# Sheet1.net
KiCad netlist of a schematic drawn in Altium Designer
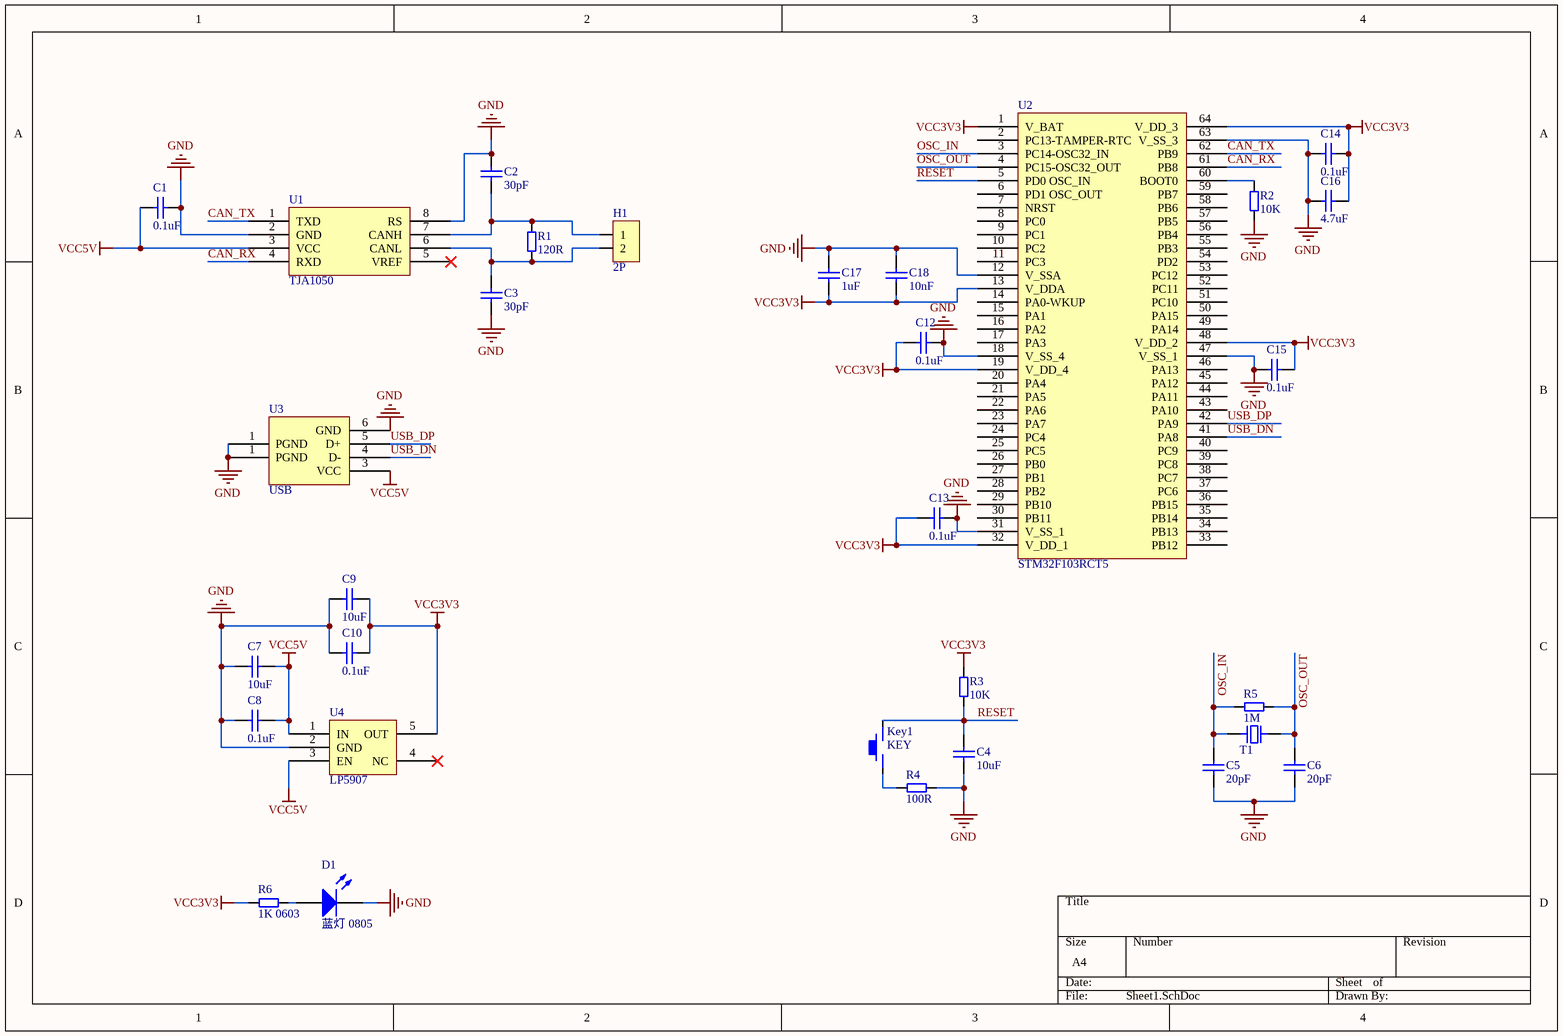
[diagram p0: Sheet1.SchDoc]

(export (version "E")
  (design (tool "Eeschema 10.0.6"))
  (components
    (comp (ref "C1")
      (value "0.1uF")
      (footprint "C1206")
      (description "贴片电容")
      (libsource (lib "WTR-SCH_LIB") (part "C"))
    )
    (comp (ref "C2")
      (value "30pF")
      (footprint "C1206")
      (description "贴片电容")
      (libsource (lib "WTR-SCH_LIB") (part "C"))
    )
    (comp (ref "C3")
      (value "30pF")
      (footprint "C1206")
      (description "贴片电容")
      (libsource (lib "WTR-SCH_LIB") (part "C"))
    )
    (comp (ref "C4")
      (value "10uF")
      (footprint "C1206")
      (description "贴片电容")
      (libsource (lib "WTR-SCH_LIB") (part "C"))
    )
    (comp (ref "C5")
      (value "20pF")
      (footprint "C1206")
      (description "贴片电容")
      (libsource (lib "WTR-SCH_LIB") (part "C"))
    )
    (comp (ref "C6")
      (value "20pF")
      (footprint "C1206")
      (description "贴片电容")
      (libsource (lib "WTR-SCH_LIB") (part "C"))
    )
    (comp (ref "C7")
      (value "10uF")
      (footprint "C1206")
      (description "贴片电容")
      (libsource (lib "WTR-SCH_LIB") (part "C"))
    )
    (comp (ref "C8")
      (value "0.1uF")
      (footprint "C1206")
      (description "贴片电容")
      (libsource (lib "WTR-SCH_LIB") (part "C"))
    )
    (comp (ref "C9")
      (value "10uF")
      (footprint "C1206")
      (description "贴片电容")
      (libsource (lib "WTR-SCH_LIB") (part "C"))
    )
    (comp (ref "C10")
      (value "0.1uF")
      (footprint "C1206")
      (description "贴片电容")
      (libsource (lib "WTR-SCH_LIB") (part "C"))
    )
    (comp (ref "C12")
      (value "0.1uF")
      (footprint "C1206")
      (description "贴片电容")
      (libsource (lib "WTR-SCH_LIB") (part "C"))
    )
    (comp (ref "C13")
      (value "0.1uF")
      (footprint "C1206")
      (description "贴片电容")
      (libsource (lib "WTR-SCH_LIB") (part "C"))
    )
    (comp (ref "C14")
      (value "0.1uF")
      (footprint "C1206")
      (description "贴片电容")
      (libsource (lib "WTR-SCH_LIB") (part "C"))
    )
    (comp (ref "C15")
      (value "0.1uF")
      (footprint "C1206")
      (description "贴片电容")
      (libsource (lib "WTR-SCH_LIB") (part "C"))
    )
    (comp (ref "C16")
      (value "4.7uF")
      (footprint "C1206")
      (description "贴片电容")
      (libsource (lib "WTR-SCH_LIB") (part "C"))
    )
    (comp (ref "C17")
      (value "1uF")
      (footprint "C1206")
      (description "贴片电容")
      (libsource (lib "WTR-SCH_LIB") (part "C"))
    )
    (comp (ref "C18")
      (value "10nF")
      (footprint "C1206")
      (description "贴片电容")
      (libsource (lib "WTR-SCH_LIB") (part "C"))
    )
    (comp (ref "D1")
      (value "蓝灯 0805")
      (footprint "0805_LED")
      (description "发光二极管")
      (libsource (lib "WTR-SCH_LIB") (part "LED"))
    )
    (comp (ref "H1") (value "2P") (footprint "PIN2") (libsource (lib "WTR-SCH_LIB") (part "2P")))
    (comp (ref "Key1")
      (value "KEY")
      (footprint "J_TS1187")
      (description "按键")
      (libsource (lib "WTR-SCH_LIB") (part "KEY"))
    )
    (comp (ref "R1")
      (value "120R")
      (footprint "R1206")
      (description "贴片电阻")
      (libsource (lib "WTR-SCH_LIB") (part "R"))
    )
    (comp (ref "R2")
      (value "10K")
      (footprint "R1206")
      (description "贴片电阻")
      (libsource (lib "WTR-SCH_LIB") (part "R"))
    )
    (comp (ref "R3")
      (value "10K")
      (footprint "R1206")
      (description "贴片电阻")
      (libsource (lib "WTR-SCH_LIB") (part "R"))
    )
    (comp (ref "R4")
      (value "100R")
      (footprint "R1206")
      (description "贴片电阻")
      (libsource (lib "WTR-SCH_LIB") (part "R"))
    )
    (comp (ref "R5")
      (value "1M")
      (footprint "R1206")
      (description "贴片电阻")
      (libsource (lib "WTR-SCH_LIB") (part "R"))
    )
    (comp (ref "R6")
      (value "1K 0603")
      (footprint "R1206")
      (description "贴片电阻")
      (libsource (lib "WTR-SCH_LIB") (part "R"))
    )
    (comp (ref "T1")
      (value "C5032")
      (footprint "CRYSTAL-SMD-5032")
      (libsource (lib "WTR-SCH_LIB") (part "C5032"))
    )
    (comp (ref "U1") (value "TJA1050") (footprint "TJA1050") (libsource (lib "WTR-SCH_LIB") (part "TJA1050")))
    (comp (ref "U2")
      (value "STM32F103RCT5")
      (footprint "TSQFP50P1200X1200X160-64N")
      (libsource (lib "WTR-SCH_LIB") (part "STM32F103RCT5"))
    )
    (comp (ref "U3") (value "USB") (footprint "0480371000") (libsource (lib "WTR-SCH_LIB") (part "USB")))
    (comp (ref "U4") (value "LP5907") (footprint "SOT-23-5") (libsource (lib "WTR-SCH_LIB") (part "LP5907")))
  )
  (nets
    (net (code "1") (name "/CAN_RX") (class "Default")
      (node (ref "U1") (pin "4") (pinfunction "RXD_4") (pintype "passive"))
      (node (ref "U2") (pin "61") (pinfunction "PB8_61") (pintype "passive"))
    )
    (net (code "2") (name "/CAN_TX") (class "Default")
      (node (ref "U1") (pin "1") (pinfunction "TXD_1") (pintype "passive"))
      (node (ref "U2") (pin "62") (pinfunction "PB9_62") (pintype "passive"))
    )
    (net (code "3") (name "/OSC_IN") (class "Default")
      (node (ref "C5") (pin "2") (pinfunction "2_2") (pintype "passive"))
      (node (ref "R5") (pin "1") (pinfunction "1_1") (pintype "passive"))
      (node (ref "T1") (pin "1") (pinfunction "1_1") (pintype "passive"))
      (node (ref "U2") (pin "3") (pinfunction "PC14-OSC32_IN_3") (pintype "passive"))
    )
    (net (code "4") (name "/OSC_OUT") (class "Default")
      (node (ref "C6") (pin "2") (pinfunction "2_2") (pintype "passive"))
      (node (ref "R5") (pin "2") (pinfunction "2_2") (pintype "passive"))
      (node (ref "T1") (pin "2") (pinfunction "2_2") (pintype "passive"))
      (node (ref "U2") (pin "4") (pinfunction "PC15-OSC32_OUT_4") (pintype "passive"))
    )
    (net (code "5") (name "/RESET") (class "Default")
      (node (ref "C4") (pin "2") (pinfunction "2_2") (pintype "passive"))
      (node (ref "Key1") (pin "2") (pinfunction "2_2") (pintype "passive"))
      (node (ref "R3") (pin "1") (pinfunction "1_1") (pintype "passive"))
      (node (ref "U2") (pin "5") (pinfunction "PD0_OSC_IN_5") (pintype "passive"))
    )
    (net (code "6") (name "/USB_DN") (class "Default")
      (node (ref "U2") (pin "41") (pinfunction "PA8_41") (pintype "passive"))
      (node (ref "U3") (pin "4") (pinfunction "D-_4") (pintype "passive"))
    )
    (net (code "7") (name "/USB_DP") (class "Default")
      (node (ref "U2") (pin "42") (pinfunction "PA9_42") (pintype "passive"))
      (node (ref "U3") (pin "5") (pinfunction "D+_5") (pintype "passive"))
    )
    (net (code "8") (name "GND") (class "Default")
      (node (ref "C1") (pin "2") (pinfunction "2_2") (pintype "passive"))
      (node (ref "C10") (pin "1") (pinfunction "1_1") (pintype "passive"))
      (node (ref "C12") (pin "2") (pinfunction "2_2") (pintype "passive"))
      (node (ref "C13") (pin "2") (pinfunction "2_2") (pintype "passive"))
      (node (ref "C14") (pin "1") (pinfunction "1_1") (pintype "passive"))
      (node (ref "C15") (pin "1") (pinfunction "1_1") (pintype "passive"))
      (node (ref "C16") (pin "1") (pinfunction "1_1") (pintype "passive"))
      (node (ref "C17") (pin "2") (pinfunction "2_2") (pintype "passive"))
      (node (ref "C18") (pin "2") (pinfunction "2_2") (pintype "passive"))
      (node (ref "C2") (pin "2") (pinfunction "2_2") (pintype "passive"))
      (node (ref "C3") (pin "2") (pinfunction "2_2") (pintype "passive"))
      (node (ref "C4") (pin "1") (pinfunction "1_1") (pintype "passive"))
      (node (ref "C5") (pin "1") (pinfunction "1_1") (pintype "passive"))
      (node (ref "C6") (pin "1") (pinfunction "1_1") (pintype "passive"))
      (node (ref "C7") (pin "1") (pinfunction "1_1") (pintype "passive"))
      (node (ref "C8") (pin "1") (pinfunction "1_1") (pintype "passive"))
      (node (ref "C9") (pin "1") (pinfunction "1_1") (pintype "passive"))
      (node (ref "D1") (pin "2") (pinfunction "2_2") (pintype "passive"))
      (node (ref "R2") (pin "2") (pinfunction "2_2") (pintype "passive"))
      (node (ref "R4") (pin "2") (pinfunction "2_2") (pintype "passive"))
      (node (ref "U1") (pin "2") (pinfunction "GND_2") (pintype "passive"))
      (node (ref "U1") (pin "8") (pinfunction "RS_8") (pintype "passive"))
      (node (ref "U2") (pin "12") (pinfunction "V_SSA_12") (pintype "passive"))
      (node (ref "U2") (pin "18") (pinfunction "V_SS_4_18") (pintype "passive"))
      (node (ref "U2") (pin "31") (pinfunction "V_SS_1_31") (pintype "passive"))
      (node (ref "U2") (pin "47") (pinfunction "V_SS_1_47") (pintype "passive"))
      (node (ref "U2") (pin "63") (pinfunction "V_SS_3_63") (pintype "passive"))
      (node (ref "U3") (pin "1") (pinfunction "PGND_1") (pintype "passive"))
      (node (ref "U3") (pin "6") (pinfunction "GND_6") (pintype "passive"))
      (node (ref "U4") (pin "2") (pinfunction "GND_2") (pintype "passive"))
    )
    (net (code "9") (name "Net-(D1-Pad1)") (class "Default")
      (node (ref "D1") (pin "1") (pinfunction "1_1") (pintype "passive"))
      (node (ref "R6") (pin "2") (pinfunction "2_2") (pintype "passive"))
    )
    (net (code "10") (name "Net-(Key1-Pad1)") (class "Default")
      (node (ref "Key1") (pin "1") (pinfunction "1_1") (pintype "passive"))
      (node (ref "R4") (pin "1") (pinfunction "1_1") (pintype "passive"))
    )
    (net (code "11") (name "Net-(U1-CANH)") (class "Default")
      (node (ref "C2") (pin "1") (pinfunction "1_1") (pintype "passive"))
      (node (ref "H1") (pin "1") (pinfunction "1_1") (pintype "passive"))
      (node (ref "R1") (pin "2") (pinfunction "2_2") (pintype "passive"))
      (node (ref "U1") (pin "7") (pinfunction "CANH_7") (pintype "passive"))
    )
    (net (code "12") (name "Net-(U1-CANL)") (class "Default")
      (node (ref "C3") (pin "1") (pinfunction "1_1") (pintype "passive"))
      (node (ref "H1") (pin "2") (pinfunction "2_2") (pintype "passive"))
      (node (ref "R1") (pin "1") (pinfunction "1_1") (pintype "passive"))
      (node (ref "U1") (pin "6") (pinfunction "CANL_6") (pintype "passive"))
    )
    (net (code "13") (name "Net-(U2-BOOT0)") (class "Default")
      (node (ref "R2") (pin "1") (pinfunction "1_1") (pintype "passive"))
      (node (ref "U2") (pin "60") (pinfunction "BOOT0_60") (pintype "passive"))
    )
    (net (code "14") (name "VCC3V3") (class "Default")
      (node (ref "C10") (pin "2") (pinfunction "2_2") (pintype "passive"))
      (node (ref "C12") (pin "1") (pinfunction "1_1") (pintype "passive"))
      (node (ref "C13") (pin "1") (pinfunction "1_1") (pintype "passive"))
      (node (ref "C14") (pin "2") (pinfunction "2_2") (pintype "passive"))
      (node (ref "C15") (pin "2") (pinfunction "2_2") (pintype "passive"))
      (node (ref "C16") (pin "2") (pinfunction "2_2") (pintype "passive"))
      (node (ref "C17") (pin "1") (pinfunction "1_1") (pintype "passive"))
      (node (ref "C18") (pin "1") (pinfunction "1_1") (pintype "passive"))
      (node (ref "C9") (pin "2") (pinfunction "2_2") (pintype "passive"))
      (node (ref "R3") (pin "2") (pinfunction "2_2") (pintype "passive"))
      (node (ref "R6") (pin "1") (pinfunction "1_1") (pintype "passive"))
      (node (ref "U2") (pin "1") (pinfunction "V_BAT_1") (pintype "passive"))
      (node (ref "U2") (pin "13") (pinfunction "V_DDA_13") (pintype "passive"))
      (node (ref "U2") (pin "19") (pinfunction "V_DD_4_19") (pintype "passive"))
      (node (ref "U2") (pin "32") (pinfunction "V_DD_1_32") (pintype "passive"))
      (node (ref "U2") (pin "48") (pinfunction "V_DD_2_48") (pintype "passive"))
      (node (ref "U2") (pin "64") (pinfunction "V_DD_3_64") (pintype "passive"))
      (node (ref "U4") (pin "5") (pinfunction "OUT_5") (pintype "passive"))
    )
    (net (code "15") (name "VCC5V") (class "Default")
      (node (ref "C1") (pin "1") (pinfunction "1_1") (pintype "passive"))
      (node (ref "C7") (pin "2") (pinfunction "2_2") (pintype "passive"))
      (node (ref "C8") (pin "2") (pinfunction "2_2") (pintype "passive"))
      (node (ref "U1") (pin "3") (pinfunction "VCC_3") (pintype "passive"))
      (node (ref "U3") (pin "3") (pinfunction "VCC_3") (pintype "passive"))
      (node (ref "U4") (pin "1") (pinfunction "IN_1") (pintype "passive"))
      (node (ref "U4") (pin "3") (pinfunction "EN_3") (pintype "passive"))
    )
    (net (code "16") (name "unconnected-(U1-VREF-Pad5)") (class "Default")
      (node (ref "U1") (pin "5") (pinfunction "VREF_5") (pintype "passive+no_connect"))
    )
    (net (code "17") (name "unconnected-(U2-NRST-Pad7)") (class "Default")
      (node (ref "U2") (pin "7") (pinfunction "NRST_7") (pintype "passive"))
    )
    (net (code "18") (name "unconnected-(U2-PA0-WKUP-Pad14)") (class "Default")
      (node (ref "U2") (pin "14") (pinfunction "PA0-WKUP_14") (pintype "passive"))
    )
    (net (code "19") (name "unconnected-(U2-PA1-Pad15)") (class "Default")
      (node (ref "U2") (pin "15") (pinfunction "PA1_15") (pintype "passive"))
    )
    (net (code "20") (name "unconnected-(U2-PA2-Pad16)") (class "Default")
      (node (ref "U2") (pin "16") (pinfunction "PA2_16") (pintype "passive"))
    )
    (net (code "21") (name "unconnected-(U2-PA3-Pad17)") (class "Default")
      (node (ref "U2") (pin "17") (pinfunction "PA3_17") (pintype "passive"))
    )
    (net (code "22") (name "unconnected-(U2-PA4-Pad20)") (class "Default")
      (node (ref "U2") (pin "20") (pinfunction "PA4_20") (pintype "passive"))
    )
    (net (code "23") (name "unconnected-(U2-PA5-Pad21)") (class "Default")
      (node (ref "U2") (pin "21") (pinfunction "PA5_21") (pintype "passive"))
    )
    (net (code "24") (name "unconnected-(U2-PA6-Pad22)") (class "Default")
      (node (ref "U2") (pin "22") (pinfunction "PA6_22") (pintype "passive"))
    )
    (net (code "25") (name "unconnected-(U2-PA7-Pad23)") (class "Default")
      (node (ref "U2") (pin "23") (pinfunction "PA7_23") (pintype "passive"))
    )
    (net (code "26") (name "unconnected-(U2-PA10-Pad43)") (class "Default")
      (node (ref "U2") (pin "43") (pinfunction "PA10_43") (pintype "passive"))
    )
    (net (code "27") (name "unconnected-(U2-PA11-Pad44)") (class "Default")
      (node (ref "U2") (pin "44") (pinfunction "PA11_44") (pintype "passive"))
    )
    (net (code "28") (name "unconnected-(U2-PA12-Pad45)") (class "Default")
      (node (ref "U2") (pin "45") (pinfunction "PA12_45") (pintype "passive"))
    )
    (net (code "29") (name "unconnected-(U2-PA13-Pad46)") (class "Default")
      (node (ref "U2") (pin "46") (pinfunction "PA13_46") (pintype "passive"))
    )
    (net (code "30") (name "unconnected-(U2-PA14-Pad49)") (class "Default")
      (node (ref "U2") (pin "49") (pinfunction "PA14_49") (pintype "passive"))
    )
    (net (code "31") (name "unconnected-(U2-PA15-Pad50)") (class "Default")
      (node (ref "U2") (pin "50") (pinfunction "PA15_50") (pintype "passive"))
    )
    (net (code "32") (name "unconnected-(U2-PB0-Pad26)") (class "Default")
      (node (ref "U2") (pin "26") (pinfunction "PB0_26") (pintype "passive"))
    )
    (net (code "33") (name "unconnected-(U2-PB1-Pad27)") (class "Default")
      (node (ref "U2") (pin "27") (pinfunction "PB1_27") (pintype "passive"))
    )
    (net (code "34") (name "unconnected-(U2-PB2-Pad28)") (class "Default")
      (node (ref "U2") (pin "28") (pinfunction "PB2_28") (pintype "passive"))
    )
    (net (code "35") (name "unconnected-(U2-PB3-Pad55)") (class "Default")
      (node (ref "U2") (pin "55") (pinfunction "PB3_55") (pintype "passive"))
    )
    (net (code "36") (name "unconnected-(U2-PB4-Pad56)") (class "Default")
      (node (ref "U2") (pin "56") (pinfunction "PB4_56") (pintype "passive"))
    )
    (net (code "37") (name "unconnected-(U2-PB5-Pad57)") (class "Default")
      (node (ref "U2") (pin "57") (pinfunction "PB5_57") (pintype "passive"))
    )
    (net (code "38") (name "unconnected-(U2-PB6-Pad58)") (class "Default")
      (node (ref "U2") (pin "58") (pinfunction "PB6_58") (pintype "passive"))
    )
    (net (code "39") (name "unconnected-(U2-PB7-Pad59)") (class "Default")
      (node (ref "U2") (pin "59") (pinfunction "PB7_59") (pintype "passive"))
    )
    (net (code "40") (name "unconnected-(U2-PB10-Pad29)") (class "Default")
      (node (ref "U2") (pin "29") (pinfunction "PB10_29") (pintype "passive"))
    )
    (net (code "41") (name "unconnected-(U2-PB11-Pad30)") (class "Default")
      (node (ref "U2") (pin "30") (pinfunction "PB11_30") (pintype "passive"))
    )
    (net (code "42") (name "unconnected-(U2-PB12-Pad33)") (class "Default")
      (node (ref "U2") (pin "33") (pinfunction "PB12_33") (pintype "passive"))
    )
    (net (code "43") (name "unconnected-(U2-PB13-Pad34)") (class "Default")
      (node (ref "U2") (pin "34") (pinfunction "PB13_34") (pintype "passive"))
    )
    (net (code "44") (name "unconnected-(U2-PB14-Pad35)") (class "Default")
      (node (ref "U2") (pin "35") (pinfunction "PB14_35") (pintype "passive"))
    )
    (net (code "45") (name "unconnected-(U2-PB15-Pad36)") (class "Default")
      (node (ref "U2") (pin "36") (pinfunction "PB15_36") (pintype "passive"))
    )
    (net (code "46") (name "unconnected-(U2-PC0-Pad8)") (class "Default")
      (node (ref "U2") (pin "8") (pinfunction "PC0_8") (pintype "passive"))
    )
    (net (code "47") (name "unconnected-(U2-PC1-Pad9)") (class "Default")
      (node (ref "U2") (pin "9") (pinfunction "PC1_9") (pintype "passive"))
    )
    (net (code "48") (name "unconnected-(U2-PC2-Pad10)") (class "Default")
      (node (ref "U2") (pin "10") (pinfunction "PC2_10") (pintype "passive"))
    )
    (net (code "49") (name "unconnected-(U2-PC3-Pad11)") (class "Default")
      (node (ref "U2") (pin "11") (pinfunction "PC3_11") (pintype "passive"))
    )
    (net (code "50") (name "unconnected-(U2-PC4-Pad24)") (class "Default")
      (node (ref "U2") (pin "24") (pinfunction "PC4_24") (pintype "passive"))
    )
    (net (code "51") (name "unconnected-(U2-PC5-Pad25)") (class "Default")
      (node (ref "U2") (pin "25") (pinfunction "PC5_25") (pintype "passive"))
    )
    (net (code "52") (name "unconnected-(U2-PC6-Pad37)") (class "Default")
      (node (ref "U2") (pin "37") (pinfunction "PC6_37") (pintype "passive"))
    )
    (net (code "53") (name "unconnected-(U2-PC7-Pad38)") (class "Default")
      (node (ref "U2") (pin "38") (pinfunction "PC7_38") (pintype "passive"))
    )
    (net (code "54") (name "unconnected-(U2-PC8-Pad39)") (class "Default")
      (node (ref "U2") (pin "39") (pinfunction "PC8_39") (pintype "passive"))
    )
    (net (code "55") (name "unconnected-(U2-PC9-Pad40)") (class "Default")
      (node (ref "U2") (pin "40") (pinfunction "PC9_40") (pintype "passive"))
    )
    (net (code "56") (name "unconnected-(U2-PC10-Pad51)") (class "Default")
      (node (ref "U2") (pin "51") (pinfunction "PC10_51") (pintype "passive"))
    )
    (net (code "57") (name "unconnected-(U2-PC11-Pad52)") (class "Default")
      (node (ref "U2") (pin "52") (pinfunction "PC11_52") (pintype "passive"))
    )
    (net (code "58") (name "unconnected-(U2-PC12-Pad53)") (class "Default")
      (node (ref "U2") (pin "53") (pinfunction "PC12_53") (pintype "passive"))
    )
    (net (code "59") (name "unconnected-(U2-PC13-TAMPER-RTC-Pad2)") (class "Default")
      (node (ref "U2") (pin "2") (pinfunction "PC13-TAMPER-RTC_2") (pintype "passive"))
    )
    (net (code "60") (name "unconnected-(U2-PD1_OSC_OUT-Pad6)") (class "Default")
      (node (ref "U2") (pin "6") (pinfunction "PD1_OSC_OUT_6") (pintype "passive"))
    )
    (net (code "61") (name "unconnected-(U2-PD2-Pad54)") (class "Default")
      (node (ref "U2") (pin "54") (pinfunction "PD2_54") (pintype "passive"))
    )
    (net (code "62") (name "unconnected-(U4-NC-Pad4)") (class "Default")
      (node (ref "U4") (pin "4") (pinfunction "NC_4") (pintype "passive+no_connect"))
    )
  )
)
